# tracksoar_slightly_smaller_chip.net
KiCad netlist of a schematic drawn in EAGLE
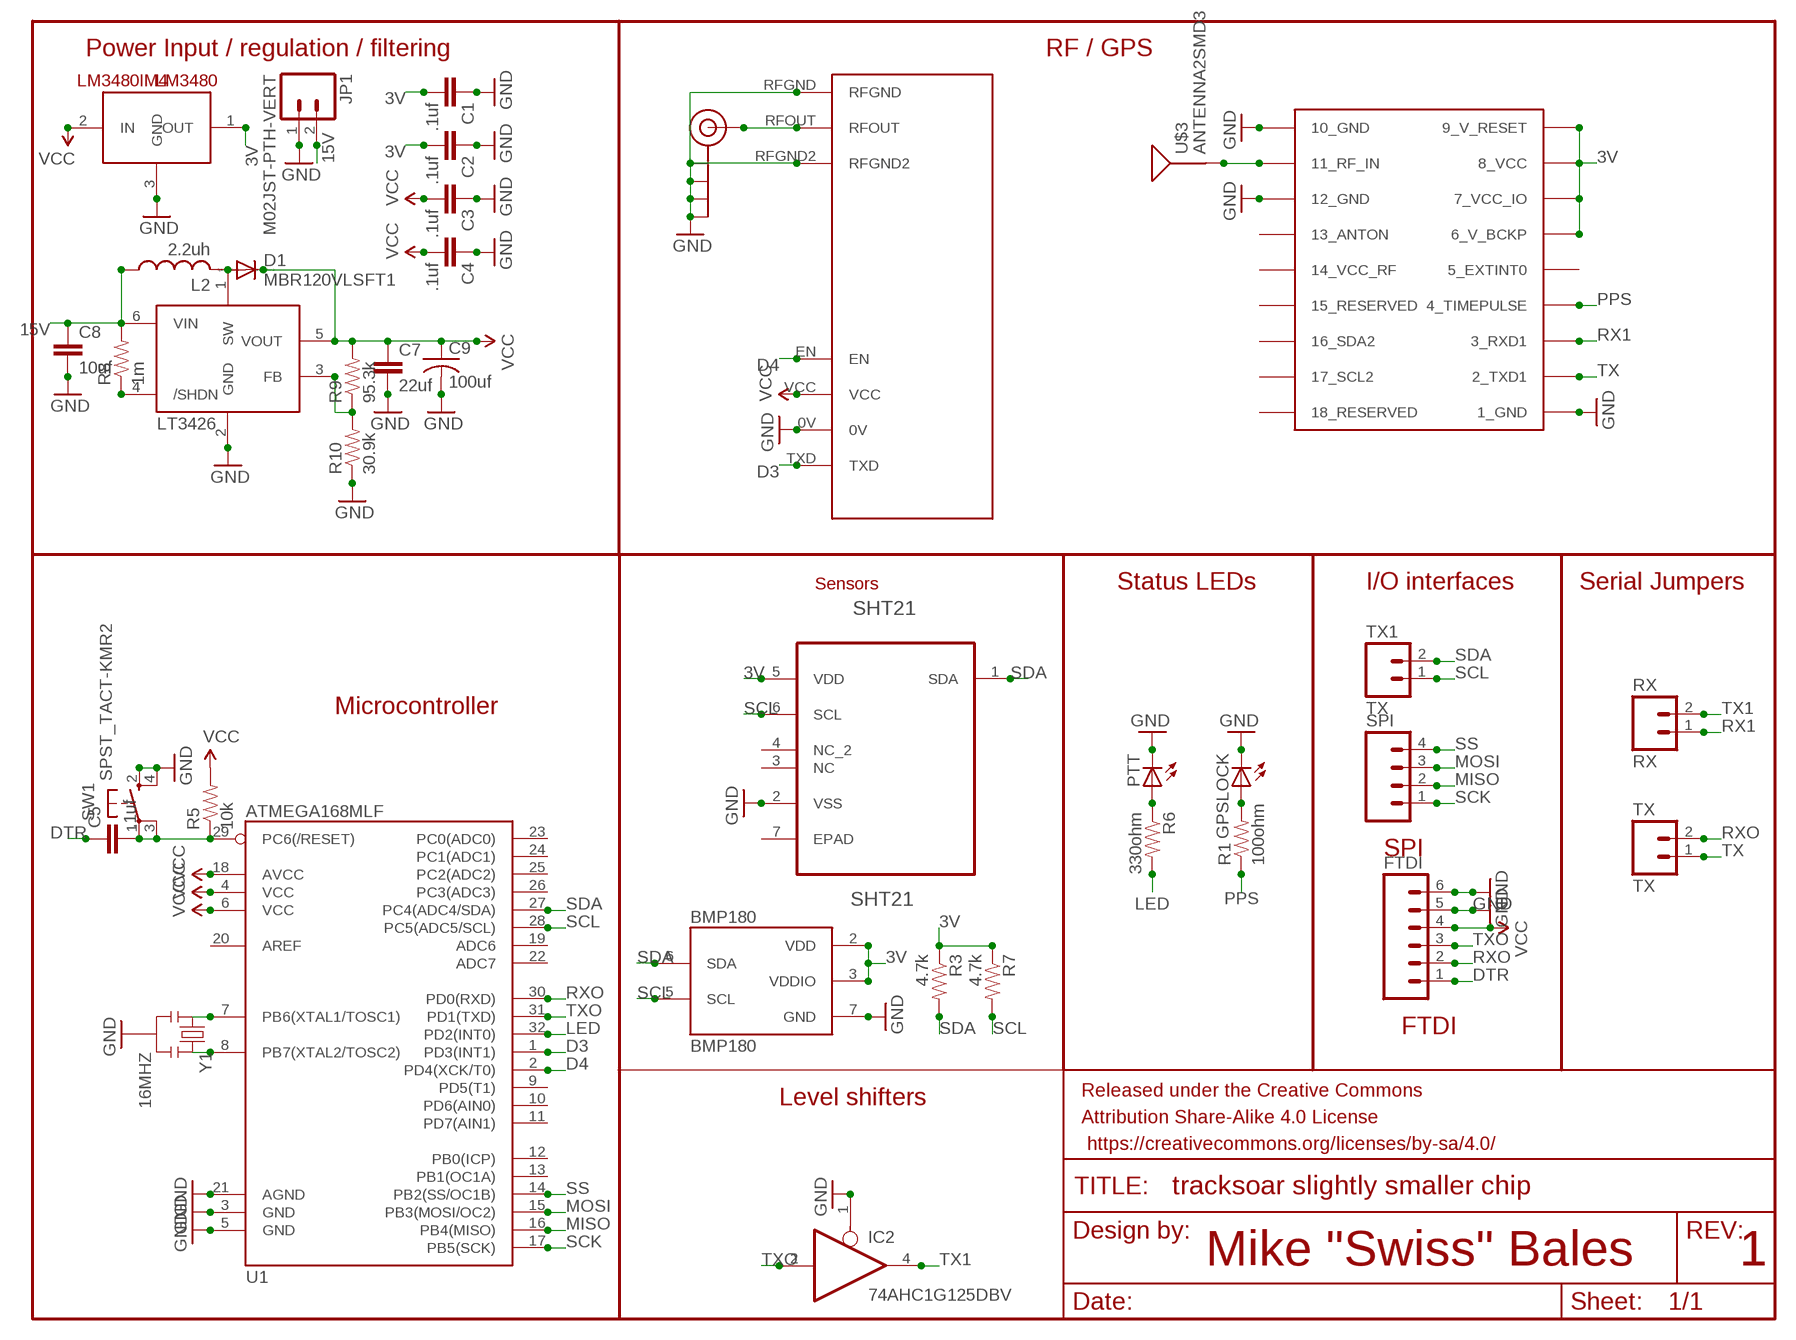
[diagram p0: schematic, sheet 1]

(export (version "E")
  (design (tool "Eeschema 10.0.6"))
  (components
    (comp (ref "BMP180")
      (value "BMP180")
      (footprint "eagle-import:BMP180")
      (libsource (lib "eagle-import") (part "BMP180"))
    )
    (comp (ref "C1")
      (value ".1uf")
      (footprint "eagle-import:0805")
      (libsource (lib "eagle-import") (part "CAP0805"))
    )
    (comp (ref "C2")
      (value ".1uf")
      (footprint "eagle-import:0805")
      (libsource (lib "eagle-import") (part "CAP0805"))
    )
    (comp (ref "C3")
      (value ".1uf")
      (footprint "eagle-import:0805")
      (libsource (lib "eagle-import") (part "CAP0805"))
    )
    (comp (ref "C4")
      (value ".1uf")
      (footprint "eagle-import:0805")
      (libsource (lib "eagle-import") (part "CAP0805"))
    )
    (comp (ref "C5")
      (value ".1uf")
      (footprint "eagle-import:0805")
      (libsource (lib "eagle-import") (part "CAP0805"))
    )
    (comp (ref "C7")
      (value "22uf")
      (footprint "eagle-import:0805")
      (libsource (lib "eagle-import") (part "CAP0805"))
    )
    (comp (ref "C8")
      (value "10uf")
      (footprint "eagle-import:0805")
      (libsource (lib "eagle-import") (part "CAP0805"))
    )
    (comp (ref "C9")
      (value "100uf")
      (footprint "eagle-import:C1206")
      (libsource (lib "eagle-import") (part "C-USC1206"))
    )
    (comp (ref "D1")
      (value "MBR120VLSFT1")
      (footprint "eagle-import:SOD123")
      (libsource (lib "eagle-import") (part "DIODE-SOD123"))
    )
    (comp (ref "FRAME1")
      (value "FRAME-LETTER")
      (footprint "eagle-import:CREATIVE_COMMONS")
      (libsource (lib "eagle-import") (part "FRAME-LETTER"))
    )
    (comp (ref "FTDI")
      (value "M06NO_SILK_FEMALE_PTH")
      (footprint "eagle-import:1X06_NO_SILK")
      (libsource (lib "eagle-import") (part "M06NO_SILK_FEMALE_PTH"))
    )
    (comp (ref "GPSLOCK")
      (value "LEDCHIP-LED0805")
      (footprint "eagle-import:CHIP-LED0805")
      (libsource (lib "eagle-import") (part "LEDCHIP-LED0805"))
    )
    (comp (ref "IC2")
      (value "74AHC1G125DBV")
      (footprint "eagle-import:SOT23-5")
      (libsource (lib "eagle-import") (part "741G125DBVAHC"))
    )
    (comp (ref "J$1")
      (value "SMA_EDGE")
      (footprint "eagle-import:SMA-EDGE")
      (libsource (lib "eagle-import") (part "SMA_EDGE"))
    )
    (comp (ref "JP1")
      (value "M02JST-PTH-VERT")
      (footprint "eagle-import:JST-2-PTH-VERT")
      (libsource (lib "eagle-import") (part "M02JST-PTH-VERT"))
    )
    (comp (ref "L2")
      (value "2.2uh")
      (footprint "eagle-import:L1812")
      (libsource (lib "eagle-import") (part "L-USL1812"))
    )
    (comp (ref "LM3480")
      (value "LM3480IM4")
      (footprint "eagle-import:SOT23-3")
      (libsource (lib "eagle-import") (part "LM3480IM4"))
    )
    (comp (ref "LT3426")
      (value "LT3426")
      (footprint "eagle-import:SOT23-6")
      (libsource (lib "eagle-import") (part "LT3426"))
    )
    (comp (ref "PTT")
      (value "LEDCHIP-LED0805")
      (footprint "eagle-import:CHIP-LED0805")
      (libsource (lib "eagle-import") (part "LEDCHIP-LED0805"))
    )
    (comp (ref "R1")
      (value "100ohm")
      (footprint "eagle-import:0805")
      (libsource (lib "eagle-import") (part "RESISTOR0805-RES"))
    )
    (comp (ref "R3")
      (value "4.7k")
      (footprint "eagle-import:0805")
      (libsource (lib "eagle-import") (part "RESISTOR0805-RES"))
    )
    (comp (ref "R5")
      (value "10k")
      (footprint "eagle-import:0805")
      (libsource (lib "eagle-import") (part "RESISTOR0805-RES"))
    )
    (comp (ref "R6")
      (value "330ohm")
      (footprint "eagle-import:0805")
      (libsource (lib "eagle-import") (part "RESISTOR0805-RES"))
    )
    (comp (ref "R7")
      (value "4.7k")
      (footprint "eagle-import:0805")
      (libsource (lib "eagle-import") (part "RESISTOR0805-RES"))
    )
    (comp (ref "R8")
      (value "1m")
      (footprint "eagle-import:0805")
      (libsource (lib "eagle-import") (part "RESISTOR0805-RES"))
    )
    (comp (ref "R9")
      (value "95.3k")
      (footprint "eagle-import:0805")
      (libsource (lib "eagle-import") (part "RESISTOR0805-RES"))
    )
    (comp (ref "R10")
      (value "30.9k")
      (footprint "eagle-import:0805")
      (libsource (lib "eagle-import") (part "RESISTOR0805-RES"))
    )
    (comp (ref "RX")
      (value "RX")
      (footprint "eagle-import:JST-2-PTH-VERT")
      (libsource (lib "eagle-import") (part "M02JST-PTH-VERT"))
    )
    (comp (ref "SHT21")
      (value "SHT21")
      (footprint "eagle-import:DFN300X300X110-7N")
      (libsource (lib "eagle-import") (part "SHT21"))
    )
    (comp (ref "SPI")
      (value "M04JST-PTH-VERT")
      (footprint "eagle-import:JST-4-PTH-VERT")
      (libsource (lib "eagle-import") (part "M04JST-PTH-VERT"))
    )
    (comp (ref "SW1")
      (value "SPST_TACT-KMR2")
      (footprint "eagle-import:KMR2")
      (libsource (lib "eagle-import") (part "SPST_TACT-KMR2"))
    )
    (comp (ref "TX")
      (value "TX")
      (footprint "eagle-import:JST-2-PTH-VERT")
      (libsource (lib "eagle-import") (part "M02JST-PTH-VERT"))
    )
    (comp (ref "TX1")
      (value "TX")
      (footprint "eagle-import:JST-2-PTH-VERT")
      (libsource (lib "eagle-import") (part "M02JST-PTH-VERT"))
    )
    (comp (ref "U$1")
      (value "UBLOX_MAX")
      (footprint "eagle-import:UBLOX_MAX")
      (libsource (lib "eagle-import") (part "UBLOX_MAX"))
    )
    (comp (ref "U$2")
      (value "RADIOMETRIX-HX1")
      (footprint "eagle-import:RADIOMETRIX-HX1")
      (libsource (lib "eagle-import") (part "RADIOMETRIX-HX1"))
    )
    (comp (ref "U$3")
      (value "ANTENNA2SMD3")
      (footprint "eagle-import:ANTENNA-CHIP4")
      (libsource (lib "eagle-import") (part "ANTENNA2SMD3"))
    )
    (comp (ref "U1")
      (value "ATMEGA168MLF")
      (footprint "eagle-import:MLF32")
      (libsource (lib "eagle-import") (part "ATMEGA168MLF"))
    )
    (comp (ref "Y1")
      (value "16MHZ")
      (footprint "eagle-import:RESONATOR-SMD")
      (libsource (lib "eagle-import") (part "RESONATOR16MHZ"))
    )
  )
  (nets
    (net (code "1") (name "/3V") (class "Default")
      (node (ref "BMP180") (pin "2") (pinfunction "VDD_2") (pintype "power_in"))
      (node (ref "BMP180") (pin "3") (pinfunction "VDDIO_3") (pintype "power_in"))
      (node (ref "C1") (pin "2") (pinfunction "2_2") (pintype "passive"))
      (node (ref "C2") (pin "2") (pinfunction "2_2") (pintype "passive"))
      (node (ref "LM3480") (pin "1") (pinfunction "OUT_1") (pintype "bidirectional"))
      (node (ref "R3") (pin "1") (pinfunction "1_1") (pintype "passive"))
      (node (ref "R7") (pin "1") (pinfunction "1_1") (pintype "passive"))
      (node (ref "SHT21") (pin "5") (pinfunction "VDD_5") (pintype "power_in"))
      (node (ref "U$1") (pin "6_V_BCKP") (pinfunction "6_V_BCKP_6_V_BCKP") (pintype "bidirectional"))
      (node (ref "U$1") (pin "7_VCC_IO") (pinfunction "7_VCC_IO_7_VCC_IO") (pintype "power_in"))
      (node (ref "U$1") (pin "8_VCC") (pinfunction "8_VCC_8_VCC") (pintype "power_in"))
      (node (ref "U$1") (pin "9_V_RESET") (pinfunction "9_V_RESET_9_V_RESET") (pintype "power_in"))
    )
    (net (code "2") (name "/15V") (class "Default")
      (node (ref "C8") (pin "1") (pinfunction "1_1") (pintype "passive"))
      (node (ref "JP1") (pin "2") (pinfunction "2_2") (pintype "passive"))
      (node (ref "L2") (pin "1") (pinfunction "1_1") (pintype "passive"))
      (node (ref "LT3426") (pin "6") (pinfunction "VIN_6") (pintype "input"))
      (node (ref "R8") (pin "2") (pinfunction "2_2") (pintype "passive"))
    )
    (net (code "3") (name "/D3") (class "Default")
      (node (ref "U$2") (pin "TXD") (pinfunction "TXD_TXD") (pintype "bidirectional"))
      (node (ref "U1") (pin "1") (pinfunction "PD3(INT1)_1") (pintype "bidirectional"))
    )
    (net (code "4") (name "/D4") (class "Default")
      (node (ref "U$2") (pin "EN") (pinfunction "EN_EN") (pintype "bidirectional"))
      (node (ref "U1") (pin "2") (pinfunction "PD4(XCK/T0)_2") (pintype "bidirectional"))
    )
    (net (code "5") (name "/DTR") (class "Default")
      (node (ref "C5") (pin "1") (pinfunction "1_1") (pintype "passive"))
      (node (ref "FTDI") (pin "1") (pinfunction "1_1") (pintype "passive"))
    )
    (net (code "6") (name "/LED") (class "Default")
      (node (ref "R6") (pin "2") (pinfunction "2_2") (pintype "passive"))
      (node (ref "U1") (pin "32") (pinfunction "PD2(INT0)_32") (pintype "bidirectional"))
    )
    (net (code "7") (name "/MISO") (class "Default")
      (node (ref "SPI") (pin "2") (pinfunction "2_2") (pintype "passive"))
      (node (ref "U1") (pin "16") (pinfunction "PB4(MISO)_16") (pintype "bidirectional"))
    )
    (net (code "8") (name "/MOSI") (class "Default")
      (node (ref "SPI") (pin "3") (pinfunction "3_3") (pintype "passive"))
      (node (ref "U1") (pin "15") (pinfunction "PB3(MOSI/OC2)_15") (pintype "bidirectional"))
    )
    (net (code "9") (name "/PPS") (class "Default")
      (node (ref "R1") (pin "1") (pinfunction "1_1") (pintype "passive"))
      (node (ref "U$1") (pin "4_TIMEPULSE") (pinfunction "4_TIMEPULSE_4_TIMEPULSE") (pintype "bidirectional"))
    )
    (net (code "10") (name "/RX1") (class "Default")
      (node (ref "RX") (pin "1") (pinfunction "1_1") (pintype "passive"))
      (node (ref "U$1") (pin "3_RXD1") (pinfunction "3_RXD1_3_RXD1") (pintype "bidirectional"))
    )
    (net (code "11") (name "/RXO") (class "Default")
      (node (ref "FTDI") (pin "2") (pinfunction "2_2") (pintype "passive"))
      (node (ref "TX") (pin "2") (pinfunction "2_2") (pintype "passive"))
      (node (ref "U1") (pin "30") (pinfunction "PD0(RXD)_30") (pintype "bidirectional"))
    )
    (net (code "12") (name "/SCK") (class "Default")
      (node (ref "SPI") (pin "1") (pinfunction "1_1") (pintype "passive"))
      (node (ref "U1") (pin "17") (pinfunction "PB5(SCK)_17") (pintype "bidirectional"))
    )
    (net (code "13") (name "/SCL") (class "Default")
      (node (ref "BMP180") (pin "5") (pinfunction "SCL_5") (pintype "input"))
      (node (ref "R7") (pin "2") (pinfunction "2_2") (pintype "passive"))
      (node (ref "SHT21") (pin "6") (pinfunction "SCL_6") (pintype "input"))
      (node (ref "TX1") (pin "1") (pinfunction "1_1") (pintype "passive"))
      (node (ref "U1") (pin "28") (pinfunction "PC5(ADC5/SCL)_28") (pintype "bidirectional"))
    )
    (net (code "14") (name "/SDA") (class "Default")
      (node (ref "BMP180") (pin "6") (pinfunction "SDA_6") (pintype "bidirectional"))
      (node (ref "R3") (pin "2") (pinfunction "2_2") (pintype "passive"))
      (node (ref "SHT21") (pin "1") (pinfunction "SDA_1") (pintype "bidirectional"))
      (node (ref "TX1") (pin "2") (pinfunction "2_2") (pintype "passive"))
      (node (ref "U1") (pin "27") (pinfunction "PC4(ADC4/SDA)_27") (pintype "bidirectional"))
    )
    (net (code "15") (name "/SS") (class "Default")
      (node (ref "SPI") (pin "4") (pinfunction "4_4") (pintype "passive"))
      (node (ref "U1") (pin "14") (pinfunction "PB2(SS/OC1B)_14") (pintype "bidirectional"))
    )
    (net (code "16") (name "/TX") (class "Default")
      (node (ref "TX") (pin "1") (pinfunction "1_1") (pintype "passive"))
      (node (ref "U$1") (pin "2_TXD1") (pinfunction "2_TXD1_2_TXD1") (pintype "bidirectional"))
    )
    (net (code "17") (name "/TX1") (class "Default")
      (node (ref "IC2") (pin "4") (pinfunction "O_4") (pintype "tri_state"))
      (node (ref "RX") (pin "2") (pinfunction "2_2") (pintype "passive"))
    )
    (net (code "18") (name "/TXO") (class "Default")
      (node (ref "FTDI") (pin "3") (pinfunction "3_3") (pintype "passive"))
      (node (ref "IC2") (pin "2") (pinfunction "I_2") (pintype "input"))
      (node (ref "U1") (pin "31") (pinfunction "PD1(TXD)_31") (pintype "bidirectional"))
    )
    (net (code "19") (name "GND") (class "Default")
      (node (ref "BMP180") (pin "7") (pinfunction "GND_7") (pintype "power_in"))
      (node (ref "C1") (pin "1") (pinfunction "1_1") (pintype "passive"))
      (node (ref "C2") (pin "1") (pinfunction "1_1") (pintype "passive"))
      (node (ref "C3") (pin "1") (pinfunction "1_1") (pintype "passive"))
      (node (ref "C4") (pin "1") (pinfunction "1_1") (pintype "passive"))
      (node (ref "C7") (pin "2") (pinfunction "2_2") (pintype "passive"))
      (node (ref "C8") (pin "2") (pinfunction "2_2") (pintype "passive"))
      (node (ref "C9") (pin "2") (pinfunction "2_2") (pintype "passive"))
      (node (ref "FTDI") (pin "5") (pinfunction "5_5") (pintype "passive"))
      (node (ref "FTDI") (pin "6") (pinfunction "6_6") (pintype "passive"))
      (node (ref "GPSLOCK") (pin "C") (pinfunction "C_C") (pintype "passive"))
      (node (ref "IC2") (pin "1") (pinfunction "OE_1") (pintype "input"))
      (node (ref "J$1") (pin "GND@0") (pinfunction "GND_GND@0") (pintype "bidirectional"))
      (node (ref "J$1") (pin "GND@1") (pinfunction "GND_GND@1") (pintype "bidirectional"))
      (node (ref "J$1") (pin "GND@2") (pinfunction "GND_GND@2") (pintype "bidirectional"))
      (node (ref "J$1") (pin "GND@3") (pinfunction "GND_GND@3") (pintype "bidirectional"))
      (node (ref "JP1") (pin "1") (pinfunction "1_1") (pintype "passive"))
      (node (ref "LM3480") (pin "3") (pinfunction "GND_3") (pintype "bidirectional"))
      (node (ref "LT3426") (pin "2") (pinfunction "GND_2") (pintype "power_in"))
      (node (ref "PTT") (pin "C") (pinfunction "C_C") (pintype "passive"))
      (node (ref "R10") (pin "1") (pinfunction "1_1") (pintype "passive"))
      (node (ref "SHT21") (pin "2") (pinfunction "VSS_2") (pintype "power_in"))
      (node (ref "SW1") (pin "2") (pinfunction "S_2") (pintype "passive"))
      (node (ref "SW1") (pin "4") (pinfunction "S1_4") (pintype "passive"))
      (node (ref "U$1") (pin "10_GND") (pinfunction "10_GND_10_GND") (pintype "power_in"))
      (node (ref "U$1") (pin "12_GND") (pinfunction "12_GND_12_GND") (pintype "power_in"))
      (node (ref "U$1") (pin "1_GND") (pinfunction "1_GND_1_GND") (pintype "power_in"))
      (node (ref "U$2") (pin "0V") (pinfunction "0V_0V") (pintype "bidirectional"))
      (node (ref "U$2") (pin "RFGND") (pinfunction "RFGND_RFGND") (pintype "bidirectional"))
      (node (ref "U$2") (pin "RFGND2") (pinfunction "RFGND2_RFGND2") (pintype "bidirectional"))
      (node (ref "U1") (pin "21") (pinfunction "AGND_21") (pintype "bidirectional"))
      (node (ref "U1") (pin "3") (pinfunction "GND_3") (pintype "bidirectional"))
      (node (ref "U1") (pin "5") (pinfunction "GND_5") (pintype "bidirectional"))
      (node (ref "Y1") (pin "2") (pinfunction "2_2") (pintype "passive"))
    )
    (net (code "20") (name "Net-(GPSLOCK-PadA)") (class "Default")
      (node (ref "GPSLOCK") (pin "A") (pinfunction "A_A") (pintype "passive"))
      (node (ref "R1") (pin "2") (pinfunction "2_2") (pintype "passive"))
    )
    (net (code "21") (name "Net-(J$1-SIGNAL)") (class "Default")
      (node (ref "J$1") (pin "SIG") (pinfunction "SIGNAL_SIG") (pintype "bidirectional"))
      (node (ref "U$2") (pin "RFOUT") (pinfunction "RFOUT_RFOUT") (pintype "bidirectional"))
    )
    (net (code "22") (name "Net-(LT3426-FB)") (class "Default")
      (node (ref "LT3426") (pin "3") (pinfunction "FB_3") (pintype "input"))
      (node (ref "R10") (pin "2") (pinfunction "2_2") (pintype "passive"))
      (node (ref "R9") (pin "1") (pinfunction "1_1") (pintype "passive"))
    )
    (net (code "23") (name "Net-(LT3426-SW)") (class "Default")
      (node (ref "D1") (pin "A") (pinfunction "A_A") (pintype "passive"))
      (node (ref "L2") (pin "2") (pinfunction "2_2") (pintype "passive"))
      (node (ref "LT3426") (pin "1") (pinfunction "SW_1") (pintype "output"))
    )
    (net (code "24") (name "Net-(LT3426-{slash}SHDN)") (class "Default")
      (node (ref "LT3426") (pin "4") (pinfunction "/SHDN_4") (pintype "input"))
      (node (ref "R8") (pin "1") (pinfunction "1_1") (pintype "passive"))
    )
    (net (code "25") (name "Net-(PTT-PadA)") (class "Default")
      (node (ref "PTT") (pin "A") (pinfunction "A_A") (pintype "passive"))
      (node (ref "R6") (pin "1") (pinfunction "1_1") (pintype "passive"))
    )
    (net (code "26") (name "Net-(SW1-P)") (class "Default")
      (node (ref "C5") (pin "2") (pinfunction "2_2") (pintype "passive"))
      (node (ref "R5") (pin "1") (pinfunction "1_1") (pintype "passive"))
      (node (ref "SW1") (pin "1") (pinfunction "P_1") (pintype "passive"))
      (node (ref "SW1") (pin "3") (pinfunction "P1_3") (pintype "passive"))
      (node (ref "U1") (pin "29") (pinfunction "PC6(/RESET)_29") (pintype "bidirectional"))
    )
    (net (code "27") (name "Net-(U$3-SIGNAL)") (class "Default")
      (node (ref "U$1") (pin "11_RF_IN") (pinfunction "11_RF_IN_11_RF_IN") (pintype "bidirectional"))
      (node (ref "U$3") (pin "SIG") (pinfunction "SIGNAL_SIG") (pintype "bidirectional"))
    )
    (net (code "28") (name "Net-(U1-PB6(XTAL1{slash}TOSC1))") (class "Default")
      (node (ref "U1") (pin "7") (pinfunction "PB6(XTAL1/TOSC1)_7") (pintype "bidirectional"))
      (node (ref "Y1") (pin "1") (pinfunction "1_1") (pintype "passive"))
    )
    (net (code "29") (name "Net-(U1-PB7(XTAL2{slash}TOSC2))") (class "Default")
      (node (ref "U1") (pin "8") (pinfunction "PB7(XTAL2/TOSC2)_8") (pintype "bidirectional"))
      (node (ref "Y1") (pin "3") (pinfunction "3_3") (pintype "passive"))
    )
    (net (code "30") (name "VCC") (class "Default")
      (node (ref "C3") (pin "2") (pinfunction "2_2") (pintype "passive"))
      (node (ref "C4") (pin "2") (pinfunction "2_2") (pintype "passive"))
      (node (ref "C7") (pin "1") (pinfunction "1_1") (pintype "passive"))
      (node (ref "C9") (pin "1") (pinfunction "1_1") (pintype "passive"))
      (node (ref "D1") (pin "C") (pinfunction "C_C") (pintype "passive"))
      (node (ref "FTDI") (pin "4") (pinfunction "4_4") (pintype "passive"))
      (node (ref "LM3480") (pin "2") (pinfunction "IN_2") (pintype "bidirectional"))
      (node (ref "LT3426") (pin "5") (pinfunction "VOUT_5") (pintype "output"))
      (node (ref "R5") (pin "2") (pinfunction "2_2") (pintype "passive"))
      (node (ref "R9") (pin "2") (pinfunction "2_2") (pintype "passive"))
      (node (ref "U$2") (pin "VCC") (pinfunction "VCC_VCC") (pintype "bidirectional"))
      (node (ref "U1") (pin "18") (pinfunction "AVCC_18") (pintype "bidirectional"))
      (node (ref "U1") (pin "4") (pinfunction "VCC_4") (pintype "bidirectional"))
      (node (ref "U1") (pin "6") (pinfunction "VCC_6") (pintype "bidirectional"))
    )
    (net (code "31") (name "unconnected-(SHT21-EPAD-Pad7)") (class "Default")
      (node (ref "SHT21") (pin "7") (pinfunction "EPAD_7") (pintype "passive"))
    )
    (net (code "32") (name "unconnected-(SHT21-NC-Pad3)") (class "Default")
      (node (ref "SHT21") (pin "3") (pinfunction "NC_3") (pintype "no_connect"))
    )
    (net (code "33") (name "unconnected-(SHT21-NC_2-Pad4)") (class "Default")
      (node (ref "SHT21") (pin "4") (pinfunction "NC_2_4") (pintype "no_connect"))
    )
    (net (code "34") (name "unconnected-(U$1-Pad5_EXTINT0)") (class "Default")
      (node (ref "U$1") (pin "5_EXTINT0") (pinfunction "5_EXTINT0_5_EXTINT0") (pintype "bidirectional"))
    )
    (net (code "35") (name "unconnected-(U$1-Pad13_ANTON)") (class "Default")
      (node (ref "U$1") (pin "13_ANTON") (pinfunction "13_ANTON_13_ANTON") (pintype "bidirectional"))
    )
    (net (code "36") (name "unconnected-(U$1-Pad14_VCC_RF)") (class "Default")
      (node (ref "U$1") (pin "14_VCC_RF") (pinfunction "14_VCC_RF_14_VCC_RF") (pintype "bidirectional"))
    )
    (net (code "37") (name "unconnected-(U$1-Pad15_RESERVED)") (class "Default")
      (node (ref "U$1") (pin "15_RESERVED") (pinfunction "15_RESERVED_15_RESERVED") (pintype "bidirectional"))
    )
    (net (code "38") (name "unconnected-(U$1-Pad16_SDA2)") (class "Default")
      (node (ref "U$1") (pin "16_SDA2") (pinfunction "16_SDA2_16_SDA2") (pintype "bidirectional"))
    )
    (net (code "39") (name "unconnected-(U$1-Pad17_SCL2)") (class "Default")
      (node (ref "U$1") (pin "17_SCL2") (pinfunction "17_SCL2_17_SCL2") (pintype "bidirectional"))
    )
    (net (code "40") (name "unconnected-(U$1-Pad18_RESERVED)") (class "Default")
      (node (ref "U$1") (pin "18_RESERVED") (pinfunction "18_RESERVED_18_RESERVED") (pintype "bidirectional"))
    )
    (net (code "41") (name "unconnected-(U1-ADC6-Pad19)") (class "Default")
      (node (ref "U1") (pin "19") (pinfunction "ADC6_19") (pintype "bidirectional"))
    )
    (net (code "42") (name "unconnected-(U1-ADC7-Pad22)") (class "Default")
      (node (ref "U1") (pin "22") (pinfunction "ADC7_22") (pintype "bidirectional"))
    )
    (net (code "43") (name "unconnected-(U1-AREF-Pad20)") (class "Default")
      (node (ref "U1") (pin "20") (pinfunction "AREF_20") (pintype "bidirectional"))
    )
    (net (code "44") (name "unconnected-(U1-PB0(ICP)-Pad12)") (class "Default")
      (node (ref "U1") (pin "12") (pinfunction "PB0(ICP)_12") (pintype "bidirectional"))
    )
    (net (code "45") (name "unconnected-(U1-PB1(OC1A)-Pad13)") (class "Default")
      (node (ref "U1") (pin "13") (pinfunction "PB1(OC1A)_13") (pintype "bidirectional"))
    )
    (net (code "46") (name "unconnected-(U1-PC0(ADC0)-Pad23)") (class "Default")
      (node (ref "U1") (pin "23") (pinfunction "PC0(ADC0)_23") (pintype "bidirectional"))
    )
    (net (code "47") (name "unconnected-(U1-PC1(ADC1)-Pad24)") (class "Default")
      (node (ref "U1") (pin "24") (pinfunction "PC1(ADC1)_24") (pintype "bidirectional"))
    )
    (net (code "48") (name "unconnected-(U1-PC2(ADC2)-Pad25)") (class "Default")
      (node (ref "U1") (pin "25") (pinfunction "PC2(ADC2)_25") (pintype "bidirectional"))
    )
    (net (code "49") (name "unconnected-(U1-PC3(ADC3)-Pad26)") (class "Default")
      (node (ref "U1") (pin "26") (pinfunction "PC3(ADC3)_26") (pintype "bidirectional"))
    )
    (net (code "50") (name "unconnected-(U1-PD5(T1)-Pad9)") (class "Default")
      (node (ref "U1") (pin "9") (pinfunction "PD5(T1)_9") (pintype "bidirectional"))
    )
    (net (code "51") (name "unconnected-(U1-PD6(AIN0)-Pad10)") (class "Default")
      (node (ref "U1") (pin "10") (pinfunction "PD6(AIN0)_10") (pintype "bidirectional"))
    )
    (net (code "52") (name "unconnected-(U1-PD7(AIN1)-Pad11)") (class "Default")
      (node (ref "U1") (pin "11") (pinfunction "PD7(AIN1)_11") (pintype "bidirectional"))
    )
  )
)
